# IMX291.net
KiCad netlist of a schematic drawn in Altium Designer
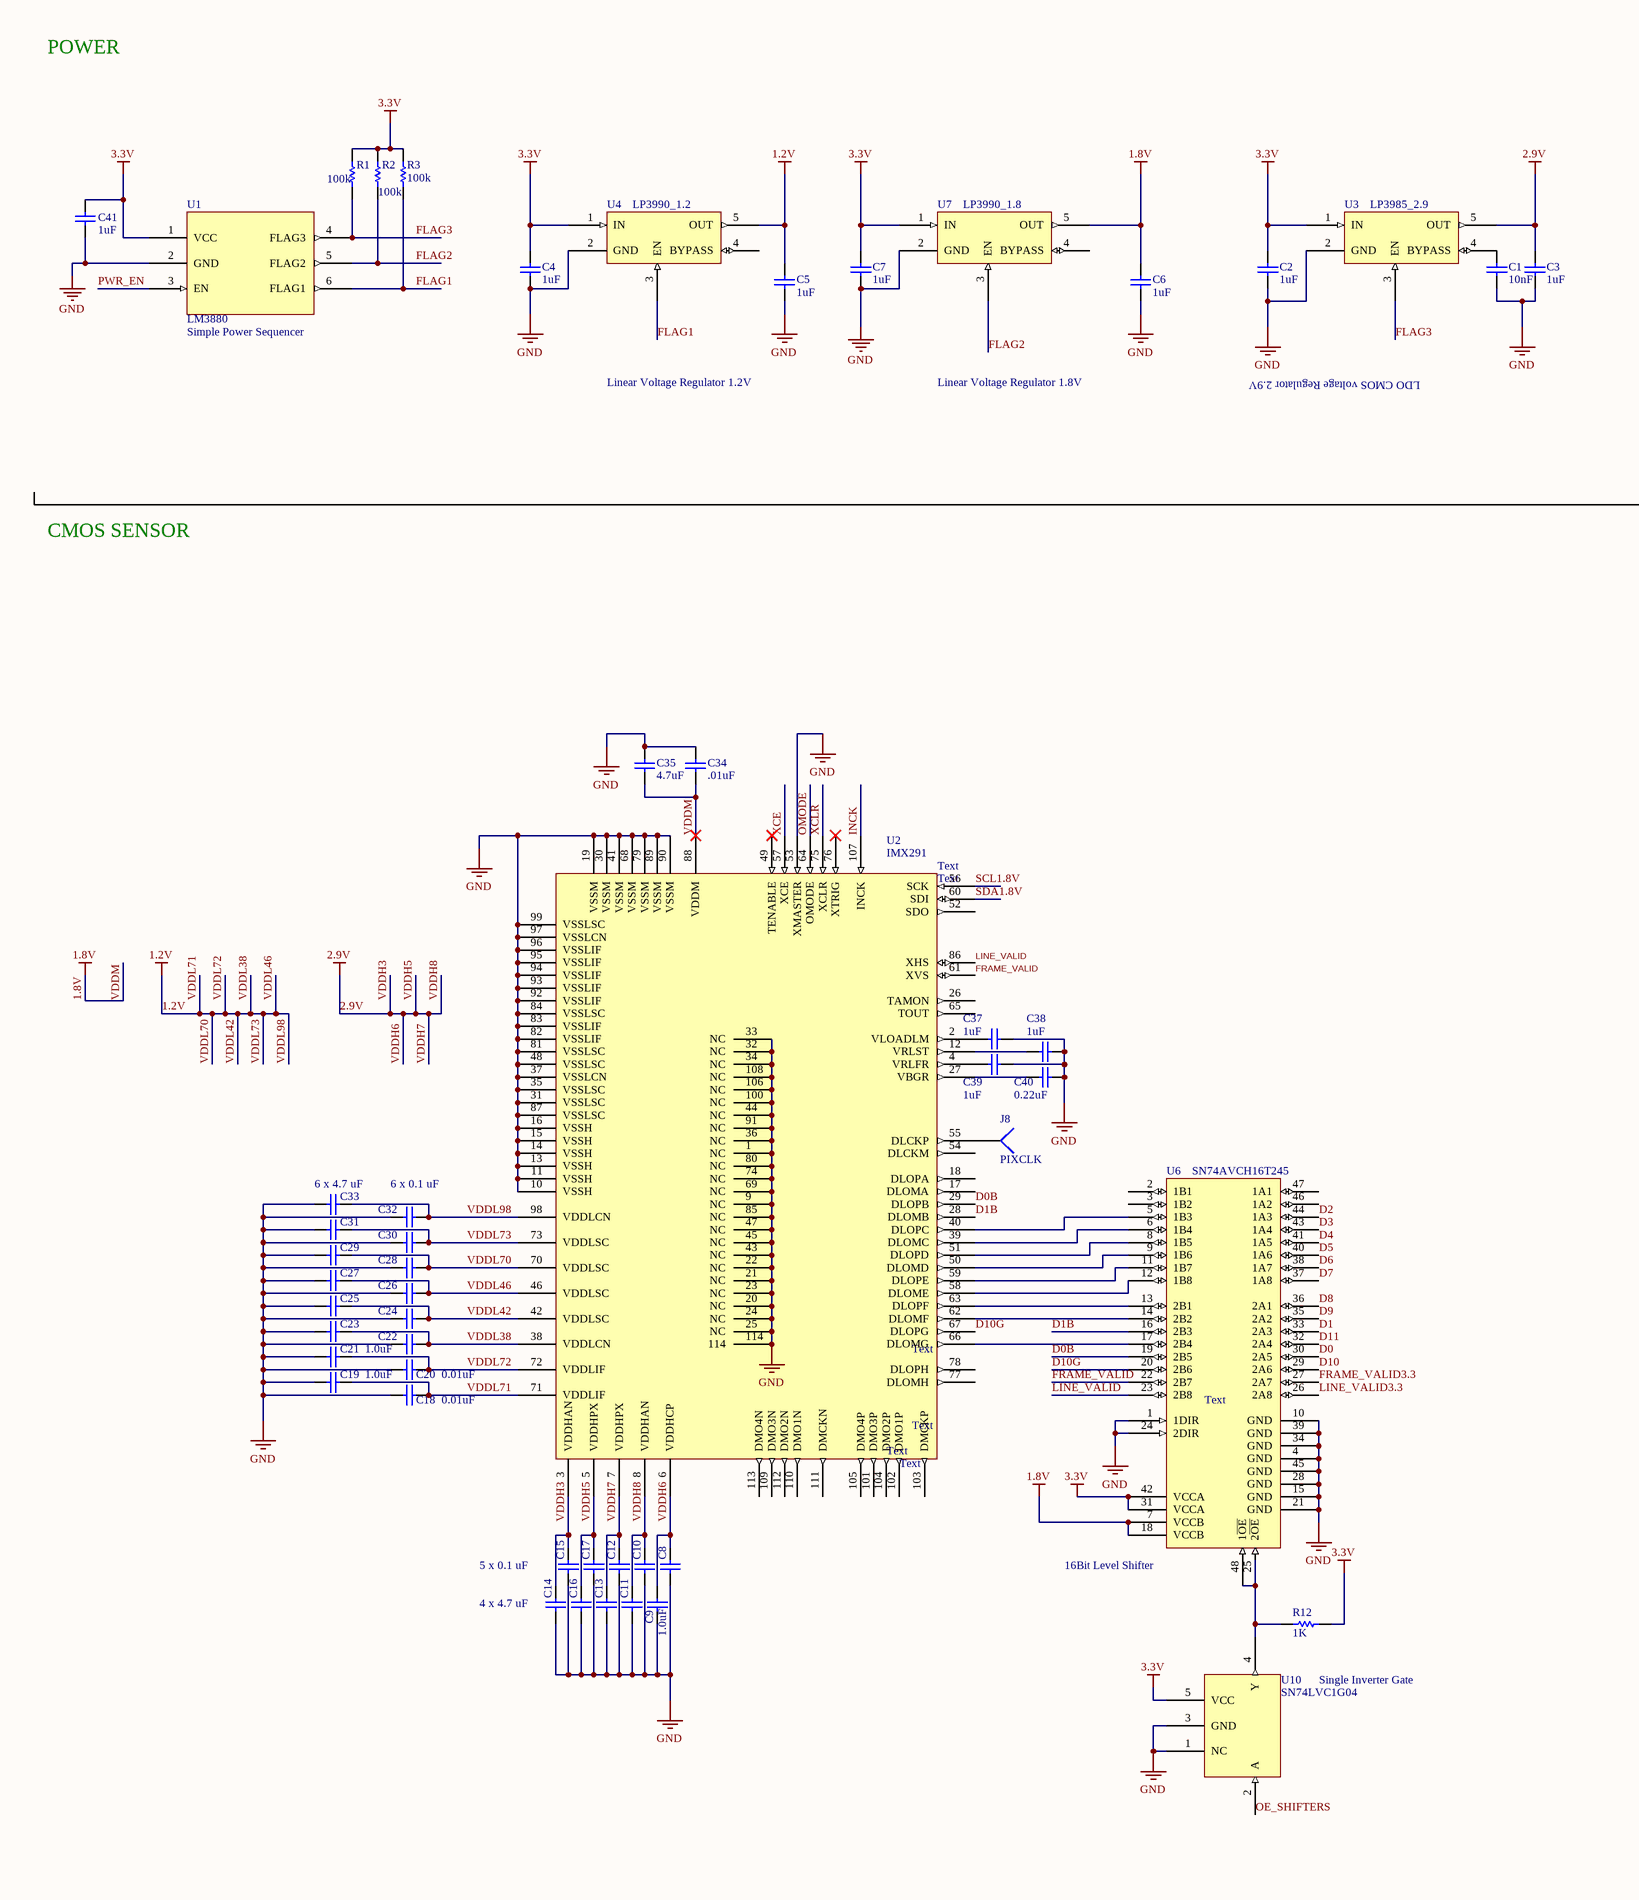
[diagram p0: IMX291.SchDoc, left]
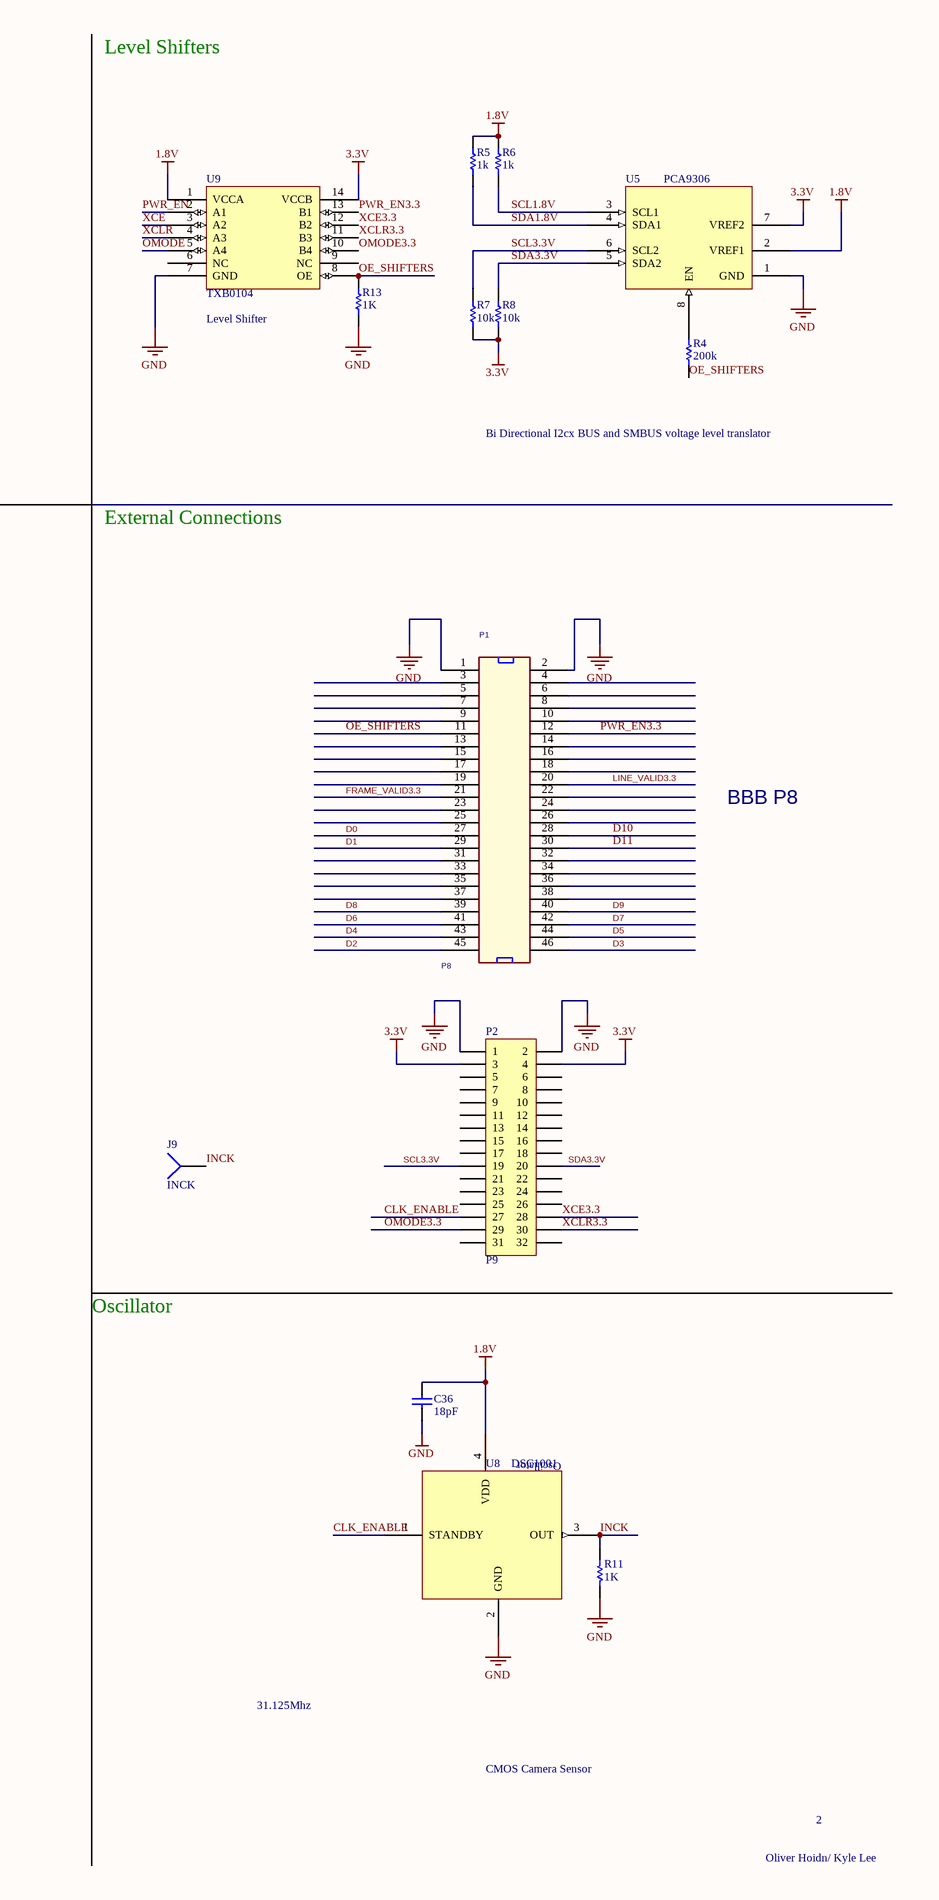
[diagram p1: IMX291.SchDoc, right]

(export (version "E")
  (design (tool "Eeschema 10.0.6"))
  (components
    (comp (ref "C1") (value "10nF") (footprint "0402") (libsource (lib "IMX291") (part "cap")))
    (comp (ref "C2") (value "1uF") (footprint "0402") (libsource (lib "IMX291") (part "cap")))
    (comp (ref "C3") (value "1uF") (footprint "0402") (libsource (lib "IMX291") (part "cap")))
    (comp (ref "C4") (value "1uF") (footprint "0402") (libsource (lib "IMX291") (part "cap")))
    (comp (ref "C5") (value "1uF") (footprint "0402") (libsource (lib "IMX291") (part "cap")))
    (comp (ref "C6") (value "1uF") (footprint "0402") (libsource (lib "IMX291") (part "cap")))
    (comp (ref "C7") (value "1uF") (footprint "0402") (libsource (lib "IMX291") (part "cap")))
    (comp (ref "C8") (value "0.1uF") (footprint "0402") (libsource (lib "IMX291") (part "cap")))
    (comp (ref "C9") (value "1.0uF") (footprint "0402") (libsource (lib "IMX291") (part "cap")))
    (comp (ref "C10") (value "0.1uF") (footprint "0402") (libsource (lib "IMX291") (part "cap")))
    (comp (ref "C11") (value "4.7uF") (footprint "0402") (libsource (lib "IMX291") (part "cap")))
    (comp (ref "C12") (value "0.1uF") (footprint "0402") (libsource (lib "IMX291") (part "cap")))
    (comp (ref "C13") (value "4.7uF") (footprint "0402") (libsource (lib "IMX291") (part "cap")))
    (comp (ref "C14") (value "4.7uF") (footprint "0402") (libsource (lib "IMX291") (part "cap")))
    (comp (ref "C15") (value "0.1uF") (footprint "0402") (libsource (lib "IMX291") (part "cap")))
    (comp (ref "C16") (value "4.7uF") (footprint "0402") (libsource (lib "IMX291") (part "cap")))
    (comp (ref "C17") (value "0.1uF") (footprint "0402") (libsource (lib "IMX291") (part "cap")))
    (comp (ref "C18") (value "0.01uF") (footprint "0402") (libsource (lib "IMX291") (part "cap")))
    (comp (ref "C19") (value "1.0uF") (footprint "0402") (libsource (lib "IMX291") (part "cap")))
    (comp (ref "C20") (value "0.01uF") (footprint "0402") (libsource (lib "IMX291") (part "cap")))
    (comp (ref "C21") (value "1.0uF") (footprint "0402") (libsource (lib "IMX291") (part "cap")))
    (comp (ref "C22") (value "0.1uF") (footprint "0402") (libsource (lib "IMX291") (part "cap")))
    (comp (ref "C23") (value "4.7uF") (footprint "0402") (libsource (lib "IMX291") (part "cap")))
    (comp (ref "C24") (value "0.1uF") (footprint "0402") (libsource (lib "IMX291") (part "cap")))
    (comp (ref "C25") (value "4.7uF") (footprint "0402") (libsource (lib "IMX291") (part "cap")))
    (comp (ref "C26") (value "0.1uF") (footprint "0402") (libsource (lib "IMX291") (part "cap")))
    (comp (ref "C27") (value "4.7uF") (footprint "0402") (libsource (lib "IMX291") (part "cap")))
    (comp (ref "C28") (value "0.1uF") (footprint "0402") (libsource (lib "IMX291") (part "cap")))
    (comp (ref "C29") (value "4.7uF") (footprint "0402") (libsource (lib "IMX291") (part "cap")))
    (comp (ref "C30") (value "0.1uF") (footprint "0402") (libsource (lib "IMX291") (part "cap")))
    (comp (ref "C31") (value "4.7uF") (footprint "0402") (libsource (lib "IMX291") (part "cap")))
    (comp (ref "C32") (value "0.1uF") (footprint "0402") (libsource (lib "IMX291") (part "cap")))
    (comp (ref "C33") (value "4.7uF") (footprint "0402") (libsource (lib "IMX291") (part "cap")))
    (comp (ref "C34") (value ".01uF") (footprint "0402") (libsource (lib "IMX291") (part "cap")))
    (comp (ref "C35") (value "4.7uF") (footprint "0402") (libsource (lib "IMX291") (part "cap")))
    (comp (ref "C36") (value "18pF") (footprint "0402") (libsource (lib "IMX291") (part "cap")))
    (comp (ref "C37") (value "1uF") (footprint "0402") (libsource (lib "IMX291") (part "cap")))
    (comp (ref "C38") (value "1uF") (footprint "0402") (libsource (lib "IMX291") (part "cap")))
    (comp (ref "C39") (value "1uF") (footprint "0402") (libsource (lib "IMX291") (part "cap")))
    (comp (ref "C40") (value "0.22uF") (footprint "0402") (libsource (lib "IMX291") (part "cap")))
    (comp (ref "C41") (value "1uF") (footprint "0402") (libsource (lib "IMX291") (part "cap")))
    (comp (ref "J8")
      (value "PIXCLK")
      (footprint "PIN1")
      (description "Socket")
      (fields (field (name "PUBLISHER") "Altium Limited"))
      (libsource (lib "IMX291") (part "Socket"))
    )
    (comp (ref "J9")
      (value "INCK")
      (footprint "PIN1")
      (description "Socket")
      (fields (field (name "PUBLISHER") "Altium Limited"))
      (libsource (lib "IMX291") (part "Socket"))
    )
    (comp (ref "P1")
      (value "P8")
      (description "CONN HEADER FMAL 46PS.1\" DL GOLD")
      (fields
        (field (name "MANUFACTURER") "Sullins Connector Solutions")
        (field (name "MANUFACTURER PART NUMBER") "PPPC232LFBN-RC")
      )
      (libsource (lib "IMX291") (part "HDR_46_F_2_0.1_0.1"))
    )
    (comp (ref "P2")
      (value "P9")
      (footprint "HDR2X16")
      (fields (field (name "PUBLISHER") "Altium Limited"))
      (libsource (lib "IMX291") (part "Header 16X2"))
    )
    (comp (ref "R1")
      (value "100k")
      (footprint "0402")
      (description "resistor")
      (libsource (lib "IMX291") (part "res"))
    )
    (comp (ref "R2")
      (value "100k")
      (footprint "0402")
      (description "resistor")
      (libsource (lib "IMX291") (part "res"))
    )
    (comp (ref "R3")
      (value "100k")
      (footprint "0402")
      (description "resistor")
      (libsource (lib "IMX291") (part "res"))
    )
    (comp (ref "R4")
      (value "200k")
      (footprint "0402")
      (description "resistor")
      (libsource (lib "IMX291") (part "res"))
    )
    (comp (ref "R5")
      (value "1k")
      (footprint "0402")
      (description "resistor")
      (libsource (lib "IMX291") (part "res"))
    )
    (comp (ref "R6")
      (value "1k")
      (footprint "0402")
      (description "resistor")
      (libsource (lib "IMX291") (part "res"))
    )
    (comp (ref "R7")
      (value "10k")
      (footprint "0603")
      (description "resistor")
      (libsource (lib "IMX291") (part "res"))
    )
    (comp (ref "R8")
      (value "10k")
      (footprint "0603")
      (description "resistor")
      (libsource (lib "IMX291") (part "res"))
    )
    (comp (ref "R11") (value "1K") (footprint "0402") (libsource (lib "") (part "res_1")))
    (comp (ref "R12") (value "1K") (footprint "0402") (libsource (lib "") (part "res_1")))
    (comp (ref "R13") (value "1K") (footprint "0402") (libsource (lib "") (part "res_1")))
    (comp (ref "U1") (value "LM3880") (footprint "SOT23-6_M") (libsource (lib "IMX291") (part "LM3880")))
    (comp (ref "U2") (value "IMX291") (footprint "SOCKET") (libsource (lib "IMX291") (part "IMX291")))
    (comp (ref "U3") (value "LP3985_2.9") (footprint "DBV005") (libsource (lib "IMX291") (part "LP3985")))
    (comp (ref "U4") (value "LP3990_1.2") (footprint "DBV005") (libsource (lib "IMX291") (part "LP3990")))
    (comp (ref "U5") (value "PCA9306") (footprint "D008_M") (libsource (lib "IMX291") (part "PCA9306")))
    (comp (ref "U6")
      (value "SN74AVCH16T245")
      (footprint "TSSOP48")
      (libsource (lib "IMX291") (part "SN74AVCH16T245"))
    )
    (comp (ref "U7") (value "LP3990_1.8") (footprint "DBV005") (libsource (lib "IMX291") (part "LP3990")))
    (comp (ref "U8") (value "DSC1001") (footprint "DSC1001") (libsource (lib "IMX291") (part "DSC1001")))
    (comp (ref "U9") (value "TXB0104") (footprint "TSSOP14_M") (libsource (lib "IMX291") (part "TXB0104")))
    (comp (ref "U10")
      (value "SN74LVC1G04")
      (footprint "DBV005")
      (libsource (lib "IMX291") (part "SN74LVC1G04"))
    )
  )
  (nets
    (net (code "1") (name "/CLK_ENABLE") (class "Default")
      (node (ref "P2") (pin "27") (pinfunction "27_27") (pintype "passive"))
      (node (ref "U8") (pin "1") (pinfunction "STANDBY_1") (pintype "passive"))
    )
    (net (code "2") (name "/D0") (class "Default")
      (node (ref "P1") (pin "27") (pinfunction "14_27") (pintype "passive"))
      (node (ref "U6") (pin "30") (pinfunction "2A5_30") (pintype "bidirectional"))
    )
    (net (code "3") (name "/D0B") (class "Default")
      (node (ref "U2") (pin "29") (pinfunction "DLOPB_29") (pintype "output"))
      (node (ref "U6") (pin "19") (pinfunction "2B5_19") (pintype "bidirectional"))
    )
    (net (code "4") (name "/D1") (class "Default")
      (node (ref "P1") (pin "29") (pinfunction "15_29") (pintype "passive"))
      (node (ref "U6") (pin "33") (pinfunction "2A3_33") (pintype "bidirectional"))
    )
    (net (code "5") (name "/D1B") (class "Default")
      (node (ref "U2") (pin "28") (pinfunction "DLOMB_28") (pintype "output"))
      (node (ref "U6") (pin "16") (pinfunction "2B3_16") (pintype "bidirectional"))
    )
    (net (code "6") (name "/D2") (class "Default")
      (node (ref "P1") (pin "45") (pinfunction "23_45") (pintype "passive"))
      (node (ref "U6") (pin "44") (pinfunction "1A3_44") (pintype "bidirectional"))
    )
    (net (code "7") (name "/D3") (class "Default")
      (node (ref "P1") (pin "46") (pinfunction "48_46") (pintype "passive"))
      (node (ref "U6") (pin "43") (pinfunction "1A4_43") (pintype "bidirectional"))
    )
    (net (code "8") (name "/D4") (class "Default")
      (node (ref "P1") (pin "43") (pinfunction "22_43") (pintype "passive"))
      (node (ref "U6") (pin "41") (pinfunction "1A5_41") (pintype "bidirectional"))
    )
    (net (code "9") (name "/D5") (class "Default")
      (node (ref "P1") (pin "44") (pinfunction "47_44") (pintype "passive"))
      (node (ref "U6") (pin "40") (pinfunction "1A6_40") (pintype "bidirectional"))
    )
    (net (code "10") (name "/D6") (class "Default")
      (node (ref "P1") (pin "41") (pinfunction "21_41") (pintype "passive"))
      (node (ref "U6") (pin "38") (pinfunction "1A7_38") (pintype "bidirectional"))
    )
    (net (code "11") (name "/D7") (class "Default")
      (node (ref "P1") (pin "42") (pinfunction "46_42") (pintype "passive"))
      (node (ref "U6") (pin "37") (pinfunction "1A8_37") (pintype "bidirectional"))
    )
    (net (code "12") (name "/D8") (class "Default")
      (node (ref "P1") (pin "39") (pinfunction "20_39") (pintype "passive"))
      (node (ref "U6") (pin "36") (pinfunction "2A1_36") (pintype "bidirectional"))
    )
    (net (code "13") (name "/D9") (class "Default")
      (node (ref "P1") (pin "40") (pinfunction "45_40") (pintype "passive"))
      (node (ref "U6") (pin "35") (pinfunction "2A2_35") (pintype "bidirectional"))
    )
    (net (code "14") (name "/D10") (class "Default")
      (node (ref "P1") (pin "28") (pinfunction "39_28") (pintype "passive"))
      (node (ref "U6") (pin "29") (pinfunction "2A6_29") (pintype "bidirectional"))
    )
    (net (code "15") (name "/D10G") (class "Default")
      (node (ref "U2") (pin "67") (pinfunction "DLOPG_67") (pintype "output"))
      (node (ref "U6") (pin "20") (pinfunction "2B6_20") (pintype "bidirectional"))
    )
    (net (code "16") (name "/D11") (class "Default")
      (node (ref "P1") (pin "30") (pinfunction "40_30") (pintype "passive"))
      (node (ref "U6") (pin "32") (pinfunction "2A4_32") (pintype "bidirectional"))
    )
    (net (code "17") (name "/FLAG1") (class "Default")
      (node (ref "R3") (pin "1") (pinfunction "1_1") (pintype "passive"))
      (node (ref "U1") (pin "6") (pinfunction "FLAG1_6") (pintype "output"))
      (node (ref "U4") (pin "3") (pinfunction "EN_3") (pintype "input"))
    )
    (net (code "18") (name "/FLAG2") (class "Default")
      (node (ref "R2") (pin "1") (pinfunction "1_1") (pintype "passive"))
      (node (ref "U1") (pin "5") (pinfunction "FLAG2_5") (pintype "output"))
      (node (ref "U7") (pin "3") (pinfunction "EN_3") (pintype "input"))
    )
    (net (code "19") (name "/FLAG3") (class "Default")
      (node (ref "R1") (pin "1") (pinfunction "1_1") (pintype "passive"))
      (node (ref "U1") (pin "4") (pinfunction "FLAG3_4") (pintype "output"))
      (node (ref "U3") (pin "3") (pinfunction "EN_3") (pintype "input"))
    )
    (net (code "20") (name "/FRAME_VALID") (class "Default")
      (node (ref "U2") (pin "61") (pinfunction "XVS_61") (pintype "bidirectional"))
      (node (ref "U6") (pin "22") (pinfunction "2B7_22") (pintype "bidirectional"))
    )
    (net (code "21") (name "/FRAME_VALID3.3") (class "Default")
      (node (ref "P1") (pin "21") (pinfunction "11_21") (pintype "passive"))
      (node (ref "U6") (pin "27") (pinfunction "2A7_27") (pintype "bidirectional"))
    )
    (net (code "22") (name "/INCK") (class "Default")
      (node (ref "J9") (pin "1") (pinfunction "1_1") (pintype "passive"))
      (node (ref "R11") (pin "2") (pinfunction "2_2") (pintype "passive"))
      (node (ref "U2") (pin "107") (pinfunction "INCK_107") (pintype "input"))
      (node (ref "U8") (pin "3") (pinfunction "OUT_3") (pintype "output"))
    )
    (net (code "23") (name "/LINE_VALID") (class "Default")
      (node (ref "U2") (pin "86") (pinfunction "XHS_86") (pintype "bidirectional"))
      (node (ref "U6") (pin "23") (pinfunction "2B8_23") (pintype "bidirectional"))
    )
    (net (code "24") (name "/LINE_VALID3.3") (class "Default")
      (node (ref "P1") (pin "20") (pinfunction "35_20") (pintype "passive"))
      (node (ref "U6") (pin "26") (pinfunction "2A8_26") (pintype "bidirectional"))
    )
    (net (code "25") (name "/OE_SHIFTERS") (class "Default")
      (node (ref "P1") (pin "11") (pinfunction "6_11") (pintype "passive"))
      (node (ref "R13") (pin "2") (pinfunction "2_2") (pintype "passive"))
      (node (ref "R4") (pin "1") (pinfunction "1_1") (pintype "passive"))
      (node (ref "U10") (pin "2") (pinfunction "A_2") (pintype "input"))
      (node (ref "U9") (pin "8") (pinfunction "OE_8") (pintype "bidirectional"))
    )
    (net (code "26") (name "/OMODE") (class "Default")
      (node (ref "U2") (pin "64") (pinfunction "OMODE_64") (pintype "input"))
      (node (ref "U9") (pin "5") (pinfunction "A4_5") (pintype "bidirectional"))
    )
    (net (code "27") (name "/OMODE3.3") (class "Default")
      (node (ref "P2") (pin "29") (pinfunction "29_29") (pintype "passive"))
      (node (ref "U9") (pin "10") (pinfunction "B4_10") (pintype "bidirectional"))
    )
    (net (code "28") (name "/PWR_EN") (class "Default")
      (node (ref "U1") (pin "3") (pinfunction "EN_3") (pintype "input"))
      (node (ref "U9") (pin "2") (pinfunction "A1_2") (pintype "bidirectional"))
    )
    (net (code "29") (name "/PWR_EN3.3") (class "Default")
      (node (ref "P1") (pin "12") (pinfunction "31_12") (pintype "passive"))
      (node (ref "U9") (pin "13") (pinfunction "B1_13") (pintype "bidirectional"))
    )
    (net (code "30") (name "/SCL1.8V") (class "Default")
      (node (ref "R6") (pin "1") (pinfunction "1_1") (pintype "passive"))
      (node (ref "U2") (pin "56") (pinfunction "SCK_56") (pintype "input"))
      (node (ref "U5") (pin "3") (pinfunction "SCL1_3") (pintype "input"))
    )
    (net (code "31") (name "/SCL3.3V") (class "Default")
      (node (ref "P2") (pin "19") (pinfunction "19_19") (pintype "passive"))
      (node (ref "R7") (pin "2") (pinfunction "2_2") (pintype "passive"))
      (node (ref "U5") (pin "6") (pinfunction "SCL2_6") (pintype "input"))
    )
    (net (code "32") (name "/SDA1.8V") (class "Default")
      (node (ref "R5") (pin "1") (pinfunction "1_1") (pintype "passive"))
      (node (ref "U2") (pin "60") (pinfunction "SDI_60") (pintype "bidirectional"))
      (node (ref "U5") (pin "4") (pinfunction "SDA1_4") (pintype "input"))
    )
    (net (code "33") (name "/SDA3.3V") (class "Default")
      (node (ref "P2") (pin "20") (pinfunction "20_20") (pintype "passive"))
      (node (ref "R8") (pin "2") (pinfunction "2_2") (pintype "passive"))
      (node (ref "U5") (pin "5") (pinfunction "SDA2_5") (pintype "input"))
    )
    (net (code "34") (name "/XCE") (class "Default")
      (node (ref "U2") (pin "57") (pinfunction "XCE_57") (pintype "input"))
      (node (ref "U9") (pin "3") (pinfunction "A2_3") (pintype "bidirectional"))
    )
    (net (code "35") (name "/XCE3.3") (class "Default")
      (node (ref "P2") (pin "28") (pinfunction "28_28") (pintype "passive"))
      (node (ref "U9") (pin "12") (pinfunction "B2_12") (pintype "bidirectional"))
    )
    (net (code "36") (name "/XCLR") (class "Default")
      (node (ref "U2") (pin "75") (pinfunction "XCLR_75") (pintype "input"))
      (node (ref "U9") (pin "4") (pinfunction "A3_4") (pintype "bidirectional"))
    )
    (net (code "37") (name "/XCLR3.3") (class "Default")
      (node (ref "P2") (pin "30") (pinfunction "30_30") (pintype "passive"))
      (node (ref "U9") (pin "11") (pinfunction "B3_11") (pintype "bidirectional"))
    )
    (net (code "38") (name "1.2V") (class "Default")
      (node (ref "C18") (pin "2") (pinfunction "2_2") (pintype "passive"))
      (node (ref "C19") (pin "2") (pinfunction "2_2") (pintype "passive"))
      (node (ref "C20") (pin "2") (pinfunction "2_2") (pintype "passive"))
      (node (ref "C21") (pin "2") (pinfunction "2_2") (pintype "passive"))
      (node (ref "C22") (pin "2") (pinfunction "2_2") (pintype "passive"))
      (node (ref "C23") (pin "2") (pinfunction "2_2") (pintype "passive"))
      (node (ref "C24") (pin "2") (pinfunction "2_2") (pintype "passive"))
      (node (ref "C25") (pin "2") (pinfunction "2_2") (pintype "passive"))
      (node (ref "C26") (pin "2") (pinfunction "2_2") (pintype "passive"))
      (node (ref "C27") (pin "2") (pinfunction "2_2") (pintype "passive"))
      (node (ref "C28") (pin "2") (pinfunction "2_2") (pintype "passive"))
      (node (ref "C29") (pin "2") (pinfunction "2_2") (pintype "passive"))
      (node (ref "C30") (pin "2") (pinfunction "2_2") (pintype "passive"))
      (node (ref "C31") (pin "2") (pinfunction "2_2") (pintype "passive"))
      (node (ref "C32") (pin "2") (pinfunction "2_2") (pintype "passive"))
      (node (ref "C33") (pin "2") (pinfunction "2_2") (pintype "passive"))
      (node (ref "C5") (pin "2") (pinfunction "2_2") (pintype "passive"))
      (node (ref "U2") (pin "38") (pinfunction "VDDLCN_38") (pintype "power_in"))
      (node (ref "U2") (pin "42") (pinfunction "VDDLSC_42") (pintype "power_in"))
      (node (ref "U2") (pin "46") (pinfunction "VDDLSC_46") (pintype "power_in"))
      (node (ref "U2") (pin "70") (pinfunction "VDDLSC_70") (pintype "power_in"))
      (node (ref "U2") (pin "71") (pinfunction "VDDLIF_71") (pintype "power_in"))
      (node (ref "U2") (pin "72") (pinfunction "VDDLIF_72") (pintype "power_in"))
      (node (ref "U2") (pin "73") (pinfunction "VDDLSC_73") (pintype "power_in"))
      (node (ref "U2") (pin "98") (pinfunction "VDDLCN_98") (pintype "power_in"))
      (node (ref "U4") (pin "5") (pinfunction "OUT_5") (pintype "output"))
    )
    (net (code "39") (name "1.8V") (class "Default")
      (node (ref "C34") (pin "1") (pinfunction "1_1") (pintype "passive"))
      (node (ref "C35") (pin "1") (pinfunction "1_1") (pintype "passive"))
      (node (ref "C36") (pin "2") (pinfunction "2_2") (pintype "passive"))
      (node (ref "C6") (pin "2") (pinfunction "2_2") (pintype "passive"))
      (node (ref "R5") (pin "2") (pinfunction "2_2") (pintype "passive"))
      (node (ref "R6") (pin "2") (pinfunction "2_2") (pintype "passive"))
      (node (ref "U2") (pin "88") (pinfunction "VDDM_88") (pintype "power_in"))
      (node (ref "U5") (pin "2") (pinfunction "VREF1_2") (pintype "power_in"))
      (node (ref "U6") (pin "18") (pinfunction "VCCB_18") (pintype "power_in"))
      (node (ref "U6") (pin "7") (pinfunction "VCCB_7") (pintype "power_in"))
      (node (ref "U7") (pin "5") (pinfunction "OUT_5") (pintype "output"))
      (node (ref "U8") (pin "4") (pinfunction "VDD_4") (pintype "passive"))
      (node (ref "U9") (pin "1") (pinfunction "VCCA_1") (pintype "power_in"))
    )
    (net (code "40") (name "2.9V") (class "Default")
      (node (ref "C10") (pin "2") (pinfunction "2_2") (pintype "passive"))
      (node (ref "C11") (pin "2") (pinfunction "2_2") (pintype "passive"))
      (node (ref "C12") (pin "2") (pinfunction "2_2") (pintype "passive"))
      (node (ref "C13") (pin "2") (pinfunction "2_2") (pintype "passive"))
      (node (ref "C14") (pin "2") (pinfunction "2_2") (pintype "passive"))
      (node (ref "C15") (pin "2") (pinfunction "2_2") (pintype "passive"))
      (node (ref "C16") (pin "2") (pinfunction "2_2") (pintype "passive"))
      (node (ref "C17") (pin "2") (pinfunction "2_2") (pintype "passive"))
      (node (ref "C3") (pin "2") (pinfunction "2_2") (pintype "passive"))
      (node (ref "C8") (pin "1") (pinfunction "1_1") (pintype "passive"))
      (node (ref "C9") (pin "1") (pinfunction "1_1") (pintype "passive"))
      (node (ref "U2") (pin "3") (pinfunction "VDDHAN_3") (pintype "power_in"))
      (node (ref "U2") (pin "5") (pinfunction "VDDHPX_5") (pintype "power_in"))
      (node (ref "U2") (pin "6") (pinfunction "VDDHCP_6") (pintype "power_in"))
      (node (ref "U2") (pin "7") (pinfunction "VDDHPX_7") (pintype "power_in"))
      (node (ref "U2") (pin "8") (pinfunction "VDDHAN_8") (pintype "power_in"))
      (node (ref "U3") (pin "5") (pinfunction "OUT_5") (pintype "output"))
    )
    (net (code "41") (name "3.3V") (class "Default")
      (node (ref "C2") (pin "1") (pinfunction "1_1") (pintype "passive"))
      (node (ref "C4") (pin "1") (pinfunction "1_1") (pintype "passive"))
      (node (ref "C41") (pin "2") (pinfunction "2_2") (pintype "passive"))
      (node (ref "C7") (pin "1") (pinfunction "1_1") (pintype "passive"))
      (node (ref "P2") (pin "3") (pinfunction "3_3") (pintype "passive"))
      (node (ref "P2") (pin "4") (pinfunction "4_4") (pintype "passive"))
      (node (ref "R1") (pin "2") (pinfunction "2_2") (pintype "passive"))
      (node (ref "R12") (pin "2") (pinfunction "2_2") (pintype "passive"))
      (node (ref "R2") (pin "2") (pinfunction "2_2") (pintype "passive"))
      (node (ref "R3") (pin "2") (pinfunction "2_2") (pintype "passive"))
      (node (ref "R7") (pin "1") (pinfunction "1_1") (pintype "passive"))
      (node (ref "R8") (pin "1") (pinfunction "1_1") (pintype "passive"))
      (node (ref "U1") (pin "1") (pinfunction "VCC_1") (pintype "power_in"))
      (node (ref "U10") (pin "5") (pinfunction "VCC_5") (pintype "power_in"))
      (node (ref "U3") (pin "1") (pinfunction "IN_1") (pintype "input"))
      (node (ref "U4") (pin "1") (pinfunction "IN_1") (pintype "input"))
      (node (ref "U5") (pin "7") (pinfunction "VREF2_7") (pintype "power_in"))
      (node (ref "U6") (pin "31") (pinfunction "VCCA_31") (pintype "power_in"))
      (node (ref "U6") (pin "42") (pinfunction "VCCA_42") (pintype "power_in"))
      (node (ref "U7") (pin "1") (pinfunction "IN_1") (pintype "input"))
      (node (ref "U9") (pin "14") (pinfunction "VCCB_14") (pintype "power_in"))
    )
    (net (code "42") (name "GND") (class "Default")
      (node (ref "C1") (pin "2") (pinfunction "2_2") (pintype "passive"))
      (node (ref "C10") (pin "1") (pinfunction "1_1") (pintype "passive"))
      (node (ref "C11") (pin "1") (pinfunction "1_1") (pintype "passive"))
      (node (ref "C12") (pin "1") (pinfunction "1_1") (pintype "passive"))
      (node (ref "C13") (pin "1") (pinfunction "1_1") (pintype "passive"))
      (node (ref "C14") (pin "1") (pinfunction "1_1") (pintype "passive"))
      (node (ref "C15") (pin "1") (pinfunction "1_1") (pintype "passive"))
      (node (ref "C16") (pin "1") (pinfunction "1_1") (pintype "passive"))
      (node (ref "C17") (pin "1") (pinfunction "1_1") (pintype "passive"))
      (node (ref "C18") (pin "1") (pinfunction "1_1") (pintype "passive"))
      (node (ref "C19") (pin "1") (pinfunction "1_1") (pintype "passive"))
      (node (ref "C2") (pin "2") (pinfunction "2_2") (pintype "passive"))
      (node (ref "C20") (pin "1") (pinfunction "1_1") (pintype "passive"))
      (node (ref "C21") (pin "1") (pinfunction "1_1") (pintype "passive"))
      (node (ref "C22") (pin "1") (pinfunction "1_1") (pintype "passive"))
      (node (ref "C23") (pin "1") (pinfunction "1_1") (pintype "passive"))
      (node (ref "C24") (pin "1") (pinfunction "1_1") (pintype "passive"))
      (node (ref "C25") (pin "1") (pinfunction "1_1") (pintype "passive"))
      (node (ref "C26") (pin "1") (pinfunction "1_1") (pintype "passive"))
      (node (ref "C27") (pin "1") (pinfunction "1_1") (pintype "passive"))
      (node (ref "C28") (pin "1") (pinfunction "1_1") (pintype "passive"))
      (node (ref "C29") (pin "1") (pinfunction "1_1") (pintype "passive"))
      (node (ref "C3") (pin "1") (pinfunction "1_1") (pintype "passive"))
      (node (ref "C30") (pin "1") (pinfunction "1_1") (pintype "passive"))
      (node (ref "C31") (pin "1") (pinfunction "1_1") (pintype "passive"))
      (node (ref "C32") (pin "1") (pinfunction "1_1") (pintype "passive"))
      (node (ref "C33") (pin "1") (pinfunction "1_1") (pintype "passive"))
      (node (ref "C34") (pin "2") (pinfunction "2_2") (pintype "passive"))
      (node (ref "C35") (pin "2") (pinfunction "2_2") (pintype "passive"))
      (node (ref "C36") (pin "1") (pinfunction "1_1") (pintype "passive"))
      (node (ref "C37") (pin "2") (pinfunction "2_2") (pintype "passive"))
      (node (ref "C38") (pin "2") (pinfunction "2_2") (pintype "passive"))
      (node (ref "C39") (pin "2") (pinfunction "2_2") (pintype "passive"))
      (node (ref "C4") (pin "2") (pinfunction "2_2") (pintype "passive"))
      (node (ref "C40") (pin "2") (pinfunction "2_2") (pintype "passive"))
      (node (ref "C41") (pin "1") (pinfunction "1_1") (pintype "passive"))
      (node (ref "C5") (pin "1") (pinfunction "1_1") (pintype "passive"))
      (node (ref "C6") (pin "1") (pinfunction "1_1") (pintype "passive"))
      (node (ref "C7") (pin "2") (pinfunction "2_2") (pintype "passive"))
      (node (ref "C8") (pin "2") (pinfunction "2_2") (pintype "passive"))
      (node (ref "C9") (pin "2") (pinfunction "2_2") (pintype "passive"))
      (node (ref "P1") (pin "1") (pinfunction "1_1") (pintype "passive"))
      (node (ref "P1") (pin "2") (pinfunction "26_2") (pintype "passive"))
      (node (ref "P2") (pin "1") (pinfunction "1_1") (pintype "passive"))
      (node (ref "P2") (pin "2") (pinfunction "2_2") (pintype "passive"))
      (node (ref "R11") (pin "1") (pinfunction "1_1") (pintype "passive"))
      (node (ref "R13") (pin "1") (pinfunction "1_1") (pintype "passive"))
      (node (ref "U1") (pin "2") (pinfunction "GND_2") (pintype "power_in"))
      (node (ref "U10") (pin "1") (pinfunction "NC_1") (pintype "passive"))
      (node (ref "U10") (pin "3") (pinfunction "GND_3") (pintype "power_in"))
      (node (ref "U2") (pin "1") (pinfunction "NC_1") (pintype "passive"))
      (node (ref "U2") (pin "10") (pinfunction "VSSH_10") (pintype "power_in"))
      (node (ref "U2") (pin "100") (pinfunction "NC_100") (pintype "passive"))
      (node (ref "U2") (pin "106") (pinfunction "NC_106") (pintype "passive"))
      (node (ref "U2") (pin "108") (pinfunction "NC_108") (pintype "passive"))
      (node (ref "U2") (pin "11") (pinfunction "VSSH_11") (pintype "power_in"))
      (node (ref "U2") (pin "114") (pinfunction "114_114") (pintype "passive"))
      (node (ref "U2") (pin "13") (pinfunction "VSSH_13") (pintype "power_in"))
      (node (ref "U2") (pin "14") (pinfunction "VSSH_14") (pintype "power_in"))
      (node (ref "U2") (pin "15") (pinfunction "VSSH_15") (pintype "power_in"))
      (node (ref "U2") (pin "16") (pinfunction "VSSH_16") (pintype "power_in"))
      (node (ref "U2") (pin "19") (pinfunction "VSSM_19") (pintype "power_in"))
      (node (ref "U2") (pin "20") (pinfunction "NC_20") (pintype "passive"))
      (node (ref "U2") (pin "21") (pinfunction "NC_21") (pintype "passive"))
      (node (ref "U2") (pin "22") (pinfunction "NC_22") (pintype "passive"))
      (node (ref "U2") (pin "23") (pinfunction "NC_23") (pintype "passive"))
      (node (ref "U2") (pin "24") (pinfunction "NC_24") (pintype "passive"))
      (node (ref "U2") (pin "25") (pinfunction "NC_25") (pintype "passive"))
      (node (ref "U2") (pin "30") (pinfunction "VSSM_30") (pintype "power_in"))
      (node (ref "U2") (pin "31") (pinfunction "VSSLSC_31") (pintype "power_in"))
      (node (ref "U2") (pin "32") (pinfunction "NC_32") (pintype "passive"))
      (node (ref "U2") (pin "33") (pinfunction "NC_33") (pintype "passive"))
      (node (ref "U2") (pin "34") (pinfunction "NC_34") (pintype "passive"))
      (node (ref "U2") (pin "35") (pinfunction "VSSLSC_35") (pintype "power_in"))
      (node (ref "U2") (pin "36") (pinfunction "NC_36") (pintype "passive"))
      (node (ref "U2") (pin "37") (pinfunction "VSSLCN_37") (pintype "power_in"))
      (node (ref "U2") (pin "41") (pinfunction "VSSM_41") (pintype "power_in"))
      (node (ref "U2") (pin "43") (pinfunction "NC_43") (pintype "passive"))
      (node (ref "U2") (pin "44") (pinfunction "NC_44") (pintype "passive"))
      (node (ref "U2") (pin "45") (pinfunction "NC_45") (pintype "passive"))
      (node (ref "U2") (pin "47") (pinfunction "NC_47") (pintype "passive"))
      (node (ref "U2") (pin "48") (pinfunction "VSSLSC_48") (pintype "power_in"))
      (node (ref "U2") (pin "53") (pinfunction "XMASTER_53") (pintype "input"))
      (node (ref "U2") (pin "68") (pinfunction "VSSM_68") (pintype "power_in"))
      (node (ref "U2") (pin "69") (pinfunction "NC_69") (pintype "passive"))
      (node (ref "U2") (pin "74") (pinfunction "NC_74") (pintype "passive"))
      (node (ref "U2") (pin "79") (pinfunction "VSSM_79") (pintype "power_in"))
      (node (ref "U2") (pin "80") (pinfunction "NC_80") (pintype "passive"))
      (node (ref "U2") (pin "81") (pinfunction "VSSLSC_81") (pintype "power_in"))
      (node (ref "U2") (pin "82") (pinfunction "VSSLIF_82") (pintype "power_in"))
      (node (ref "U2") (pin "83") (pinfunction "VSSLIF_83") (pintype "power_in"))
      (node (ref "U2") (pin "84") (pinfunction "VSSLSC_84") (pintype "power_in"))
      (node (ref "U2") (pin "85") (pinfunction "NC_85") (pintype "passive"))
      (node (ref "U2") (pin "87") (pinfunction "VSSLSC_87") (pintype "power_in"))
      (node (ref "U2") (pin "89") (pinfunction "VSSM_89") (pintype "power_in"))
      (node (ref "U2") (pin "9") (pinfunction "NC_9") (pintype "passive"))
      (node (ref "U2") (pin "90") (pinfunction "VSSM_90") (pintype "power_in"))
      (node (ref "U2") (pin "91") (pinfunction "NC_91") (pintype "passive"))
      (node (ref "U2") (pin "92") (pinfunction "VSSLIF_92") (pintype "power_in"))
      (node (ref "U2") (pin "93") (pinfunction "VSSLIF_93") (pintype "power_in"))
      (node (ref "U2") (pin "94") (pinfunction "VSSLIF_94") (pintype "power_in"))
      (node (ref "U2") (pin "95") (pinfunction "VSSLIF_95") (pintype "power_in"))
      (node (ref "U2") (pin "96") (pinfunction "VSSLIF_96") (pintype "power_in"))
      (node (ref "U2") (pin "97") (pinfunction "VSSLCN_97") (pintype "power_in"))
      (node (ref "U2") (pin "99") (pinfunction "VSSLSC_99") (pintype "power_in"))
      (node (ref "U3") (pin "2") (pinfunction "GND_2") (pintype "power_in"))
      (node (ref "U4") (pin "2") (pinfunction "GND_2") (pintype "power_in"))
      (node (ref "U5") (pin "1") (pinfunction "GND_1") (pintype "power_in"))
      (node (ref "U6") (pin "1") (pinfunction "1DIR_1") (pintype "input"))
      (node (ref "U6") (pin "10") (pinfunction "GND_10") (pintype "power_in"))
      (node (ref "U6") (pin "15") (pinfunction "GND_15") (pintype "power_in"))
      (node (ref "U6") (pin "21") (pinfunction "GND_21") (pintype "power_in"))
      (node (ref "U6") (pin "24") (pinfunction "2DIR_24") (pintype "input"))
      (node (ref "U6") (pin "28") (pinfunction "GND_28") (pintype "power_in"))
      (node (ref "U6") (pin "34") (pinfunction "GND_34") (pintype "power_in"))
      (node (ref "U6") (pin "39") (pinfunction "GND_39") (pintype "power_in"))
      (node (ref "U6") (pin "4") (pinfunction "GND_4") (pintype "power_in"))
      (node (ref "U6") (pin "45") (pinfunction "GND_45") (pintype "power_in"))
      (node (ref "U7") (pin "2") (pinfunction "GND_2") (pintype "power_in"))
      (node (ref "U8") (pin "2") (pinfunction "GND_2") (pintype "passive"))
      (node (ref "U9") (pin "7") (pinfunction "GND_7") (pintype "power_in"))
    )
    (net (code "43") (name "Net-(U2-DLCKP)") (class "Default")
      (node (ref "J8") (pin "1") (pinfunction "1_1") (pintype "passive"))
      (node (ref "U2") (pin "55") (pinfunction "DLCKP_55") (pintype "output"))
    )
    (net (code "44") (name "Net-(U2-DLOMC)") (class "Default")
      (node (ref "U2") (pin "39") (pinfunction "DLOMC_39") (pintype "output"))
      (node (ref "U6") (pin "6") (pinfunction "1B4_6") (pintype "bidirectional"))
    )
    (net (code "45") (name "Net-(U2-DLOMD)") (class "Default")
      (node (ref "U2") (pin "50") (pinfunction "DLOMD_50") (pintype "output"))
      (node (ref "U6") (pin "9") (pinfunction "1B6_9") (pintype "bidirectional"))
    )
    (net (code "46") (name "Net-(U2-DLOME)") (class "Default")
      (node (ref "U2") (pin "58") (pinfunction "DLOME_58") (pintype "output"))
      (node (ref "U6") (pin "12") (pinfunction "1B8_12") (pintype "bidirectional"))
    )
    (net (code "47") (name "Net-(U2-DLOMF)") (class "Default")
      (node (ref "U2") (pin "62") (pinfunction "DLOMF_62") (pintype "output"))
      (node (ref "U6") (pin "14") (pinfunction "2B2_14") (pintype "bidirectional"))
    )
    (net (code "48") (name "Net-(U2-DLOMG)") (class "Default")
      (node (ref "U2") (pin "66") (pinfunction "DLOMG_66") (pintype "output"))
      (node (ref "U6") (pin "17") (pinfunction "2B4_17") (pintype "bidirectional"))
    )
    (net (code "49") (name "Net-(U2-DLOPC)") (class "Default")
      (node (ref "U2") (pin "40") (pinfunction "DLOPC_40") (pintype "output"))
      (node (ref "U6") (pin "5") (pinfunction "1B3_5") (pintype "bidirectional"))
    )
    (net (code "50") (name "Net-(U2-DLOPD)") (class "Default")
      (node (ref "U2") (pin "51") (pinfunction "DLOPD_51") (pintype "output"))
      (node (ref "U6") (pin "8") (pinfunction "1B5_8") (pintype "bidirectional"))
    )
    (net (code "51") (name "Net-(U2-DLOPE)") (class "Default")
      (node (ref "U2") (pin "59") (pinfunction "DLOPE_59") (pintype "output"))
      (node (ref "U6") (pin "11") (pinfunction "1B7_11") (pintype "bidirectional"))
    )
    (net (code "52") (name "Net-(U2-DLOPF)") (class "Default")
      (node (ref "U2") (pin "63") (pinfunction "DLOPF_63") (pintype "output"))
      (node (ref "U6") (pin "13") (pinfunction "2B1_13") (pintype "bidirectional"))
    )
    (net (code "53") (name "Net-(U2-VBGR)") (class "Default")
      (node (ref "C40") (pin "1") (pinfunction "1_1") (pintype "passive"))
      (node (ref "U2") (pin "27") (pinfunction "VBGR_27") (pintype "output"))
    )
    (net (code "54") (name "Net-(U2-VLOADLM)") (class "Default")
      (node (ref "C37") (pin "1") (pinfunction "1_1") (pintype "passive"))
      (node (ref "U2") (pin "2") (pinfunction "VLOADLM_2") (pintype "output"))
    )
    (net (code "55") (name "Net-(U2-VRLFR)") (class "Default")
      (node (ref "C39") (pin "1") (pinfunction "1_1") (pintype "passive"))
      (node (ref "U2") (pin "4") (pinfunction "VRLFR_4") (pintype "output"))
    )
    (net (code "56") (name "Net-(U2-VRLST)") (class "Default")
      (node (ref "C38") (pin "1") (pinfunction "1_1") (pintype "passive"))
      (node (ref "U2") (pin "12") (pinfunction "VRLST_12") (pintype "output"))
    )
    (net (code "57") (name "Net-(U3-BYPASS)") (class "Default")
      (node (ref "C1") (pin "1") (pinfunction "1_1") (pintype "passive"))
      (node (ref "U3") (pin "4") (pinfunction "BYPASS_4") (pintype "bidirectional"))
    )
    (net (code "58") (name "Net-(U5-EN)") (class "Default")
      (node (ref "R4") (pin "2") (pinfunction "2_2") (pintype "passive"))
      (node (ref "U5") (pin "8") (pinfunction "EN_8") (pintype "input"))
    )
    (net (code "59") (name "Net-(U10-Y)") (class "Default")
      (node (ref "R12") (pin "1") (pinfunction "1_1") (pintype "passive"))
      (node (ref "U10") (pin "4") (pinfunction "Y_4") (pintype "output"))
      (node (ref "U6") (pin "25") (pinfunction "2~{OE}_25") (pintype "input"))
      (node (ref "U6") (pin "48") (pinfunction "1~{OE}_48") (pintype "input"))
    )
    (net (code "60") (name "unconnected-(P1-2-Pad3)") (class "Default")
      (node (ref "P1") (pin "3") (pinfunction "2_3") (pintype "passive"))
    )
    (net (code "61") (name "unconnected-(P1-3-Pad5)") (class "Default")
      (node (ref "P1") (pin "5") (pinfunction "3_5") (pintype "passive"))
    )
    (net (code "62") (name "unconnected-(P1-4-Pad7)") (class "Default")
      (node (ref "P1") (pin "7") (pinfunction "4_7") (pintype "passive"))
    )
    (net (code "63") (name "unconnected-(P1-5-Pad9)") (class "Default")
      (node (ref "P1") (pin "9") (pinfunction "5_9") (pintype "passive"))
    )
    (net (code "64") (name "unconnected-(P1-7-Pad13)") (class "Default")
      (node (ref "P1") (pin "13") (pinfunction "7_13") (pintype "passive"))
    )
    (net (code "65") (name "unconnected-(P1-8-Pad15)") (class "Default")
      (node (ref "P1") (pin "15") (pinfunction "8_15") (pintype "passive"))
    )
    (net (code "66") (name "unconnected-(P1-9-Pad17)") (class "Default")
      (node (ref "P1") (pin "17") (pinfunction "9_17") (pintype "passive"))
    )
    (net (code "67") (name "unconnected-(P1-10-Pad19)") (class "Default")
      (node (ref "P1") (pin "19") (pinfunction "10_19") (pintype "passive"))
    )
    (net (code "68") (name "unconnected-(P1-12-Pad23)") (class "Default")
      (node (ref "P1") (pin "23") (pinfunction "12_23") (pintype "passive"))
    )
    (net (code "69") (name "unconnected-(P1-13-Pad25)") (class "Default")
      (node (ref "P1") (pin "25") (pinfunction "13_25") (pintype "passive"))
    )
    (net (code "70") (name "unconnected-(P1-16-Pad31)") (class "Default")
      (node (ref "P1") (pin "31") (pinfunction "16_31") (pintype "passive"))
    )
    (net (code "71") (name "unconnected-(P1-17-Pad33)") (class "Default")
      (node (ref "P1") (pin "33") (pinfunction "17_33") (pintype "passive"))
    )
    (net (code "72") (name "unconnected-(P1-18-Pad35)") (class "Default")
      (node (ref "P1") (pin "35") (pinfunction "18_35") (pintype "passive"))
    )
    (net (code "73") (name "unconnected-(P1-19-Pad37)") (class "Default")
      (node (ref "P1") (pin "37") (pinfunction "19_37") (pintype "passive"))
    )
    (net (code "74") (name "unconnected-(P1-27-Pad4)") (class "Default")
      (node (ref "P1") (pin "4") (pinfunction "27_4") (pintype "passive"))
    )
    (net (code "75") (name "unconnected-(P1-28-Pad6)") (class "Default")
      (node (ref "P1") (pin "6") (pinfunction "28_6") (pintype "passive"))
    )
    (net (code "76") (name "unconnected-(P1-29-Pad8)") (class "Default")
      (node (ref "P1") (pin "8") (pinfunction "29_8") (pintype "passive"))
    )
    (net (code "77") (name "unconnected-(P1-30-Pad10)") (class "Default")
      (node (ref "P1") (pin "10") (pinfunction "30_10") (pintype "passive"))
    )
    (net (code "78") (name "unconnected-(P1-32-Pad14)") (class "Default")
      (node (ref "P1") (pin "14") (pinfunction "32_14") (pintype "passive"))
    )
    (net (code "79") (name "unconnected-(P1-33-Pad16)") (class "Default")
      (node (ref "P1") (pin "16") (pinfunction "33_16") (pintype "passive"))
    )
    (net (code "80") (name "unconnected-(P1-34-Pad18)") (class "Default")
      (node (ref "P1") (pin "18") (pinfunction "34_18") (pintype "passive"))
    )
    (net (code "81") (name "unconnected-(P1-36-Pad22)") (class "Default")
      (node (ref "P1") (pin "22") (pinfunction "36_22") (pintype "passive"))
    )
    (net (code "82") (name "unconnected-(P1-37-Pad24)") (class "Default")
      (node (ref "P1") (pin "24") (pinfunction "37_24") (pintype "passive"))
    )
    (net (code "83") (name "unconnected-(P1-38-Pad26)") (class "Default")
      (node (ref "P1") (pin "26") (pinfunction "38_26") (pintype "passive"))
    )
    (net (code "84") (name "unconnected-(P1-41-Pad32)") (class "Default")
      (node (ref "P1") (pin "32") (pinfunction "41_32") (pintype "passive"))
    )
    (net (code "85") (name "unconnected-(P1-42-Pad34)") (class "Default")
      (node (ref "P1") (pin "34") (pinfunction "42_34") (pintype "passive"))
    )
    (net (code "86") (name "unconnected-(P1-43-Pad36)") (class "Default")
      (node (ref "P1") (pin "36") (pinfunction "43_36") (pintype "passive"))
    )
    (net (code "87") (name "unconnected-(P1-44-Pad38)") (class "Default")
      (node (ref "P1") (pin "38") (pinfunction "44_38") (pintype "passive"))
    )
    (net (code "88") (name "unconnected-(P2-Pad5)") (class "Default")
      (node (ref "P2") (pin "5") (pinfunction "5_5") (pintype "passive"))
    )
    (net (code "89") (name "unconnected-(P2-Pad6)") (class "Default")
      (node (ref "P2") (pin "6") (pinfunction "6_6") (pintype "passive"))
    )
    (net (code "90") (name "unconnected-(P2-Pad7)") (class "Default")
      (node (ref "P2") (pin "7") (pinfunction "7_7") (pintype "passive"))
    )
    (net (code "91") (name "unconnected-(P2-Pad8)") (class "Default")
      (node (ref "P2") (pin "8") (pinfunction "8_8") (pintype "passive"))
    )
    (net (code "92") (name "unconnected-(P2-Pad9)") (class "Default")
      (node (ref "P2") (pin "9") (pinfunction "9_9") (pintype "passive"))
    )
    (net (code "93") (name "unconnected-(P2-Pad10)") (class "Default")
      (node (ref "P2") (pin "10") (pinfunction "10_10") (pintype "passive"))
    )
    (net (code "94") (name "unconnected-(P2-Pad11)") (class "Default")
      (node (ref "P2") (pin "11") (pinfunction "11_11") (pintype "passive"))
    )
    (net (code "95") (name "unconnected-(P2-Pad12)") (class "Default")
      (node (ref "P2") (pin "12") (pinfunction "12_12") (pintype "passive"))
    )
    (net (code "96") (name "unconnected-(P2-Pad13)") (class "Default")
      (node (ref "P2") (pin "13") (pinfunction "13_13") (pintype "passive"))
    )
    (net (code "97") (name "unconnected-(P2-Pad14)") (class "Default")
      (node (ref "P2") (pin "14") (pinfunction "14_14") (pintype "passive"))
    )
    (net (code "98") (name "unconnected-(P2-Pad15)") (class "Default")
      (node (ref "P2") (pin "15") (pinfunction "15_15") (pintype "passive"))
    )
    (net (code "99") (name "unconnected-(P2-Pad16)") (class "Default")
      (node (ref "P2") (pin "16") (pinfunction "16_16") (pintype "passive"))
    )
    (net (code "100") (name "unconnected-(P2-Pad17)") (class "Default")
      (node (ref "P2") (pin "17") (pinfunction "17_17") (pintype "passive"))
    )
    (net (code "101") (name "unconnected-(P2-Pad18)") (class "Default")
      (node (ref "P2") (pin "18") (pinfunction "18_18") (pintype "passive"))
    )
    (net (code "102") (name "unconnected-(P2-Pad21)") (class "Default")
      (node (ref "P2") (pin "21") (pinfunction "21_21") (pintype "passive"))
    )
    (net (code "103") (name "unconnected-(P2-Pad22)") (class "Default")
      (node (ref "P2") (pin "22") (pinfunction "22_22") (pintype "passive"))
    )
    (net (code "104") (name "unconnected-(P2-Pad23)") (class "Default")
      (node (ref "P2") (pin "23") (pinfunction "23_23") (pintype "passive"))
    )
    (net (code "105") (name "unconnected-(P2-Pad24)") (class "Default")
      (node (ref "P2") (pin "24") (pinfunction "24_24") (pintype "passive"))
    )
    (net (code "106") (name "unconnected-(P2-Pad25)") (class "Default")
      (node (ref "P2") (pin "25") (pinfunction "25_25") (pintype "passive"))
    )
    (net (code "107") (name "unconnected-(P2-Pad26)") (class "Default")
      (node (ref "P2") (pin "26") (pinfunction "26_26") (pintype "passive"))
    )
    (net (code "108") (name "unconnected-(P2-Pad31)") (class "Default")
      (node (ref "P2") (pin "31") (pinfunction "31_31") (pintype "passive"))
    )
    (net (code "109") (name "unconnected-(P2-Pad32)") (class "Default")
      (node (ref "P2") (pin "32") (pinfunction "32_32") (pintype "passive"))
    )
    (net (code "110") (name "unconnected-(U2-DLCKM-Pad54)") (class "Default")
      (node (ref "U2") (pin "54") (pinfunction "DLCKM_54") (pintype "output"))
    )
    (net (code "111") (name "unconnected-(U2-DLOMA-Pad17)") (class "Default")
      (node (ref "U2") (pin "17") (pinfunction "DLOMA_17") (pintype "output"))
    )
    (net (code "112") (name "unconnected-(U2-DLOMH-Pad77)") (class "Default")
      (node (ref "U2") (pin "77") (pinfunction "DLOMH_77") (pintype "output"))
    )
    (net (code "113") (name "unconnected-(U2-DLOPA-Pad18)") (class "Default")
      (node (ref "U2") (pin "18") (pinfunction "DLOPA_18") (pintype "output"))
    )
    (net (code "114") (name "unconnected-(U2-DLOPH-Pad78)") (class "Default")
      (node (ref "U2") (pin "78") (pinfunction "DLOPH_78") (pintype "output"))
    )
    (net (code "115") (name "unconnected-(U2-DMCKN-Pad111)") (class "Default")
      (node (ref "U2") (pin "111") (pinfunction "DMCKN_111") (pintype "output"))
    )
    (net (code "116") (name "unconnected-(U2-DMCKP-Pad103)") (class "Default")
      (node (ref "U2") (pin "103") (pinfunction "DMCKP_103") (pintype "output"))
    )
    (net (code "117") (name "unconnected-(U2-DMO1N-Pad110)") (class "Default")
      (node (ref "U2") (pin "110") (pinfunction "DMO1N_110") (pintype "output"))
    )
    (net (code "118") (name "unconnected-(U2-DMO1P-Pad102)") (class "Default")
      (node (ref "U2") (pin "102") (pinfunction "DMO1P_102") (pintype "output"))
    )
    (net (code "119") (name "unconnected-(U2-DMO2N-Pad112)") (class "Default")
      (node (ref "U2") (pin "112") (pinfunction "DMO2N_112") (pintype "output"))
    )
    (net (code "120") (name "unconnected-(U2-DMO2P-Pad104)") (class "Default")
      (node (ref "U2") (pin "104") (pinfunction "DMO2P_104") (pintype "output"))
    )
    (net (code "121") (name "unconnected-(U2-DMO3N-Pad109)") (class "Default")
      (node (ref "U2") (pin "109") (pinfunction "DMO3N_109") (pintype "output"))
    )
    (net (code "122") (name "unconnected-(U2-DMO3P-Pad101)") (class "Default")
      (node (ref "U2") (pin "101") (pinfunction "DMO3P_101") (pintype "output"))
    )
    (net (code "123") (name "unconnected-(U2-DMO4N-Pad113)") (class "Default")
      (node (ref "U2") (pin "113") (pinfunction "DMO4N_113") (pintype "output"))
    )
    (net (code "124") (name "unconnected-(U2-DMO4P-Pad105)") (class "Default")
      (node (ref "U2") (pin "105") (pinfunction "DMO4P_105") (pintype "output"))
    )
    (net (code "125") (name "unconnected-(U2-SDO-Pad52)") (class "Default")
      (node (ref "U2") (pin "52") (pinfunction "SDO_52") (pintype "output"))
    )
    (net (code "126") (name "unconnected-(U2-TAMON-Pad26)") (class "Default")
      (node (ref "U2") (pin "26") (pinfunction "TAMON_26") (pintype "output"))
    )
    (net (code "127") (name "unconnected-(U2-TENABLE-Pad49)") (class "Default")
      (node (ref "U2") (pin "49") (pinfunction "TENABLE_49") (pintype "input+no_connect"))
    )
    (net (code "128") (name "unconnected-(U2-TOUT-Pad65)") (class "Default")
      (node (ref "U2") (pin "65") (pinfunction "TOUT_65") (pintype "output"))
    )
    (net (code "129") (name "unconnected-(U2-XTRIG-Pad76)") (class "Default")
      (node (ref "U2") (pin "76") (pinfunction "XTRIG_76") (pintype "input+no_connect"))
    )
    (net (code "130") (name "unconnected-(U4-BYPASS-Pad4)") (class "Default")
      (node (ref "U4") (pin "4") (pinfunction "BYPASS_4") (pintype "bidirectional"))
    )
    (net (code "131") (name "unconnected-(U6-1A1-Pad47)") (class "Default")
      (node (ref "U6") (pin "47") (pinfunction "1A1_47") (pintype "bidirectional"))
    )
    (net (code "132") (name "unconnected-(U6-1A2-Pad46)") (class "Default")
      (node (ref "U6") (pin "46") (pinfunction "1A2_46") (pintype "bidirectional"))
    )
    (net (code "133") (name "unconnected-(U6-1B1-Pad2)") (class "Default")
      (node (ref "U6") (pin "2") (pinfunction "1B1_2") (pintype "bidirectional"))
    )
    (net (code "134") (name "unconnected-(U6-1B2-Pad3)") (class "Default")
      (node (ref "U6") (pin "3") (pinfunction "1B2_3") (pintype "bidirectional"))
    )
    (net (code "135") (name "unconnected-(U7-BYPASS-Pad4)") (class "Default")
      (node (ref "U7") (pin "4") (pinfunction "BYPASS_4") (pintype "bidirectional"))
    )
    (net (code "136") (name "unconnected-(U9-NC-Pad6)") (class "Default")
      (node (ref "U9") (pin "6") (pinfunction "NC_6") (pintype "passive"))
    )
    (net (code "137") (name "unconnected-(U9-NC-Pad9)") (class "Default")
      (node (ref "U9") (pin "9") (pinfunction "NC_9") (pintype "passive"))
    )
  )
)
